# WIRELESS.net
KiCad netlist of a schematic drawn in Altium Designer
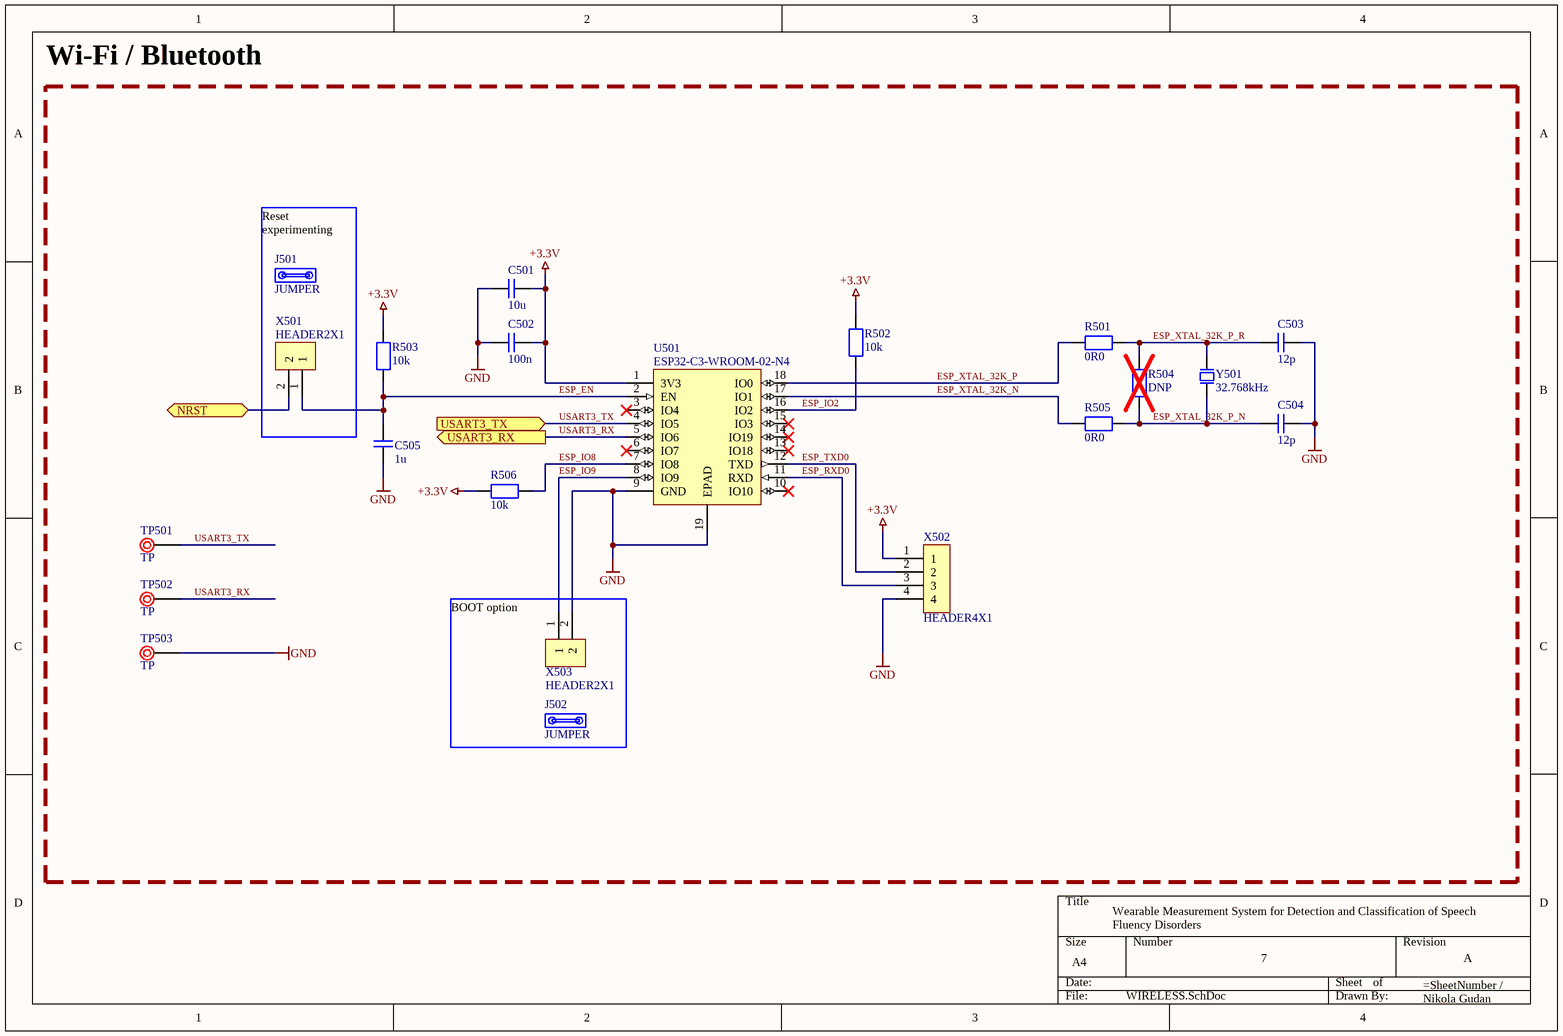
[diagram p0: WIRELESS.SchDoc]

(export (version "E")
  (design (tool "Eeschema 10.0.6"))
  (components
    (comp (ref "C501")
      (value "10u")
      (footprint "CAPC0603")
      (description "Ceramic capacitor, VAL?,  VOL?, DIEL?")
      (fields (field (name "MFR") "?") (field (name "CHECKED") "Yes"))
      (libsource (lib "NG_Passive") (part "CAPC0603"))
    )
    (comp (ref "C502")
      (value "100n")
      (footprint "CAPC0603")
      (description "Ceramic capacitor, VAL?,  VOL?, DIEL?")
      (fields (field (name "MFR") "?") (field (name "CHECKED") "Yes"))
      (libsource (lib "NG_Passive") (part "CAPC0603"))
    )
    (comp (ref "C503")
      (value "12p")
      (footprint "CAPC0603")
      (description "Ceramic capacitor, VAL?,  VOL?, DIEL?")
      (fields (field (name "MFR") "?") (field (name "CHECKED") "Yes"))
      (libsource (lib "NG_Passive") (part "CAPC0603"))
    )
    (comp (ref "C504")
      (value "12p")
      (footprint "CAPC0603")
      (description "Ceramic capacitor, VAL?,  VOL?, DIEL?")
      (fields (field (name "MFR") "?") (field (name "CHECKED") "Yes"))
      (libsource (lib "NG_Passive") (part "CAPC0603"))
    )
    (comp (ref "C505")
      (value "1u")
      (footprint "CAPC0603")
      (description "Ceramic capacitor, VAL?,  VOL?, DIEL?")
      (fields (field (name "MFR") "?") (field (name "CHECKED") "Yes"))
      (libsource (lib "NG_Passive") (part "CAPC0603"))
    )
    (comp (ref "J501")
      (value "JUMPER")
      (description "Open Top 3A 2.54mm P=2.54mm Shunts & Jumpers ROHS")
      (fields
        (field (name "MFR") "Kycon, Inc.")
        (field (name "LCSC PART NUMBER") "C5305")
        (field (name "CHECKED") "Yes")
      )
      (libsource (lib "NG_Mechanical") (part "JUMPER"))
    )
    (comp (ref "J502")
      (value "JUMPER")
      (description "Open Top 3A 2.54mm P=2.54mm Shunts & Jumpers ROHS")
      (fields
        (field (name "MFR") "Kycon, Inc.")
        (field (name "LCSC PART NUMBER") "C5305")
        (field (name "CHECKED") "Yes")
      )
      (libsource (lib "NG_Mechanical") (part "JUMPER"))
    )
    (comp (ref "R501")
      (value "0R0")
      (footprint "RESC0603")
      (description "Thick film resistor, VAL?, POW?")
      (fields (field (name "MFR") "?") (field (name "CHECKED") "Yes"))
      (libsource (lib "NG_Passive") (part "RES0603"))
    )
    (comp (ref "R502")
      (value "10k")
      (footprint "RESC0603")
      (description "Thick film resistor, VAL?, POW?")
      (fields (field (name "MFR") "?") (field (name "CHECKED") "Yes"))
      (libsource (lib "NG_Passive") (part "RES0603"))
    )
    (comp (ref "R503")
      (value "10k")
      (footprint "RESC0603")
      (description "Thick film resistor, VAL?, POW?")
      (fields (field (name "MFR") "?") (field (name "CHECKED") "Yes"))
      (libsource (lib "NG_Passive") (part "RES0603"))
    )
    (comp (ref "R504")
      (value "DNP")
      (footprint "RESC0603")
      (description "Thick film resistor, VAL?, POW?")
      (fields (field (name "MFR") "?") (field (name "CHECKED") "Yes"))
      (libsource (lib "NG_Passive") (part "RES0603"))
    )
    (comp (ref "R505")
      (value "0R0")
      (footprint "RESC0603")
      (description "Thick film resistor, VAL?, POW?")
      (fields (field (name "MFR") "?") (field (name "CHECKED") "Yes"))
      (libsource (lib "NG_Passive") (part "RES0603"))
    )
    (comp (ref "R506")
      (value "10k")
      (footprint "RESC0603")
      (description "Thick film resistor, VAL?, POW?")
      (fields (field (name "MFR") "?") (field (name "CHECKED") "Yes"))
      (libsource (lib "NG_Passive") (part "RES0603"))
    )
    (comp (ref "TP501")
      (value "TP")
      (footprint "TESTPOINT")
      (description "Testpoint")
      (fields
        (field (name "MFR") "Keystone")
        (field (name "LCSC PART NUMBER") "C238122")
        (field (name "CHECKED") "Yes")
      )
      (libsource (lib "NG_Mechanical") (part "TESTPOINT"))
    )
    (comp (ref "TP502")
      (value "TP")
      (footprint "TESTPOINT")
      (description "Testpoint")
      (fields
        (field (name "MFR") "Keystone")
        (field (name "LCSC PART NUMBER") "C238122")
        (field (name "CHECKED") "Yes")
      )
      (libsource (lib "NG_Mechanical") (part "TESTPOINT"))
    )
    (comp (ref "TP503")
      (value "TP")
      (footprint "TESTPOINT")
      (description "Testpoint")
      (fields
        (field (name "MFR") "Keystone")
        (field (name "LCSC PART NUMBER") "C238122")
        (field (name "CHECKED") "Yes")
      )
      (libsource (lib "NG_Mechanical") (part "TESTPOINT"))
    )
    (comp (ref "U501")
      (value "ESP32-C3-WROOM-02-N4")
      (footprint "ESP32-C3-WROOM-02-N4")
      (description "RF transceiver module, Bluetooth, WiFi")
      (fields
        (field (name "MFR") "Espressif Systems")
        (field (name "LCSC PART NUMBER") "C2934560")
        (field (name "CHECKED") "Yes")
      )
      (libsource (lib "NG_Digital") (part "ESP32-C3-WROOM-02-N4"))
    )
    (comp (ref "X501")
      (value "HEADER2X1")
      (footprint "HDRV2W64P254_2X1_508X254X1150")
      (description "Pin Header 2x1, P2.54")
      (fields
        (field (name "MFR") "Adam Tech")
        (field (name "LCSC PART NUMBER") "C2883961")
        (field (name "CHECKED") "Yes")
      )
      (libsource (lib "NG_Mechanical") (part "HEADER2X1"))
    )
    (comp (ref "X502")
      (value "HEADER4X1")
      (footprint "HDRV4W64P254_4X1_1016X254X1150")
      (description "Pin Header 4x1, P2.54")
      (fields (field (name "MFR") "Würth Elektronik") (field (name "CHECKED") "Yes"))
      (libsource (lib "NG_Mechanical") (part "HEADER4X1"))
    )
    (comp (ref "X503")
      (value "HEADER2X1")
      (footprint "HDRV2W64P254_2X1_508X254X1150")
      (description "Pin Header 2x1, P2.54")
      (fields
        (field (name "MFR") "Adam Tech")
        (field (name "LCSC PART NUMBER") "C2883961")
        (field (name "CHECKED") "Yes")
      )
      (libsource (lib "") (part "HEADER2X1_1"))
    )
    (comp (ref "Y501")
      (value "32.768kHz")
      (footprint "XTAL320X150X80")
      (description "Crystal, 32.768Hz, 9pF, 50kOhms")
      (fields
        (field (name "MFR") "Seiko Epson")
        (field (name "LCSC PART NUMBER") "C1987155")
        (field (name "CHECKED") "Yes")
      )
      (libsource (lib "NG_Passive") (part "X1A0001410002"))
    )
  )
  (nets
    (net (code "1") (name "+3.3V") (class "Default")
      (node (ref "C501") (pin "1") (pinfunction "1_1") (pintype "passive"))
      (node (ref "C502") (pin "1") (pinfunction "1_1") (pintype "passive"))
      (node (ref "R502") (pin "2") (pinfunction "2_2") (pintype "passive"))
      (node (ref "R503") (pin "2") (pinfunction "2_2") (pintype "passive"))
      (node (ref "R506") (pin "2") (pinfunction "2_2") (pintype "passive"))
      (node (ref "U501") (pin "1") (pinfunction "3V3_1") (pintype "power_in"))
      (node (ref "X502") (pin "1") (pinfunction "1_1") (pintype "passive"))
    )
    (net (code "2") (name "/ESP_EN") (class "Default")
      (node (ref "C505") (pin "2") (pinfunction "2_2") (pintype "passive"))
      (node (ref "R503") (pin "1") (pinfunction "1_1") (pintype "passive"))
      (node (ref "U501") (pin "2") (pinfunction "EN_2") (pintype "input"))
      (node (ref "X501") (pin "1") (pinfunction "1_1") (pintype "passive"))
    )
    (net (code "3") (name "/ESP_IO2") (class "Default")
      (node (ref "R502") (pin "1") (pinfunction "1_1") (pintype "passive"))
      (node (ref "U501") (pin "16") (pinfunction "IO2_16") (pintype "bidirectional"))
    )
    (net (code "4") (name "/ESP_IO8") (class "Default")
      (node (ref "R506") (pin "1") (pinfunction "1_1") (pintype "passive"))
      (node (ref "U501") (pin "7") (pinfunction "IO8_7") (pintype "bidirectional"))
    )
    (net (code "5") (name "/ESP_IO9") (class "Default")
      (node (ref "U501") (pin "8") (pinfunction "IO9_8") (pintype "bidirectional"))
      (node (ref "X503") (pin "1") (pinfunction "1_1") (pintype "passive"))
    )
    (net (code "6") (name "/ESP_RXD0") (class "Default")
      (node (ref "U501") (pin "11") (pinfunction "RXD_11") (pintype "input"))
      (node (ref "X502") (pin "3") (pinfunction "3_3") (pintype "passive"))
    )
    (net (code "7") (name "/ESP_TXD0") (class "Default")
      (node (ref "U501") (pin "12") (pinfunction "TXD_12") (pintype "output"))
      (node (ref "X502") (pin "2") (pinfunction "2_2") (pintype "passive"))
    )
    (net (code "8") (name "/ESP_XTAL_32K_N") (class "Default")
      (node (ref "R505") (pin "2") (pinfunction "2_2") (pintype "passive"))
      (node (ref "U501") (pin "17") (pinfunction "IO1_17") (pintype "bidirectional"))
    )
    (net (code "9") (name "/ESP_XTAL_32K_P") (class "Default")
      (node (ref "R501") (pin "2") (pinfunction "2_2") (pintype "passive"))
      (node (ref "U501") (pin "18") (pinfunction "IO0_18") (pintype "bidirectional"))
    )
    (net (code "10") (name "/ESP_XTAL_32K_P_N") (class "Default")
      (node (ref "C504") (pin "2") (pinfunction "2_2") (pintype "passive"))
      (node (ref "R504") (pin "2") (pinfunction "2_2") (pintype "passive"))
      (node (ref "R505") (pin "1") (pinfunction "1_1") (pintype "passive"))
      (node (ref "Y501") (pin "1") (pinfunction "1_1") (pintype "passive"))
    )
    (net (code "11") (name "/ESP_XTAL_32K_P_R") (class "Default")
      (node (ref "C503") (pin "2") (pinfunction "2_2") (pintype "passive"))
      (node (ref "R501") (pin "1") (pinfunction "1_1") (pintype "passive"))
      (node (ref "R504") (pin "1") (pinfunction "1_1") (pintype "passive"))
      (node (ref "Y501") (pin "2") (pinfunction "2_2") (pintype "passive"))
    )
    (net (code "12") (name "/NRST") (class "Default")
      (node (ref "X501") (pin "2") (pinfunction "2_2") (pintype "passive"))
    )
    (net (code "13") (name "/USART3_RX") (class "Default")
      (node (ref "TP502") (pin "1") (pinfunction "1_1") (pintype "passive"))
      (node (ref "U501") (pin "5") (pinfunction "IO6_5") (pintype "bidirectional"))
    )
    (net (code "14") (name "/USART3_TX") (class "Default")
      (node (ref "TP501") (pin "1") (pinfunction "1_1") (pintype "passive"))
      (node (ref "U501") (pin "4") (pinfunction "IO5_4") (pintype "bidirectional"))
    )
    (net (code "15") (name "GND") (class "Default")
      (node (ref "C501") (pin "2") (pinfunction "2_2") (pintype "passive"))
      (node (ref "C502") (pin "2") (pinfunction "2_2") (pintype "passive"))
      (node (ref "C503") (pin "1") (pinfunction "1_1") (pintype "passive"))
      (node (ref "C504") (pin "1") (pinfunction "1_1") (pintype "passive"))
      (node (ref "C505") (pin "1") (pinfunction "1_1") (pintype "passive"))
      (node (ref "TP503") (pin "1") (pinfunction "1_1") (pintype "passive"))
      (node (ref "U501") (pin "19") (pinfunction "EPAD_19") (pintype "power_in"))
      (node (ref "U501") (pin "9") (pinfunction "GND_9") (pintype "power_in"))
      (node (ref "X502") (pin "4") (pinfunction "4_4") (pintype "passive"))
      (node (ref "X503") (pin "2") (pinfunction "2_2") (pintype "passive"))
    )
    (net (code "16") (name "unconnected-(U501-IO3-Pad15)") (class "Default")
      (node (ref "U501") (pin "15") (pinfunction "IO3_15") (pintype "bidirectional+no_connect"))
    )
    (net (code "17") (name "unconnected-(U501-IO4-Pad3)") (class "Default")
      (node (ref "U501") (pin "3") (pinfunction "IO4_3") (pintype "bidirectional+no_connect"))
    )
    (net (code "18") (name "unconnected-(U501-IO7-Pad6)") (class "Default")
      (node (ref "U501") (pin "6") (pinfunction "IO7_6") (pintype "bidirectional+no_connect"))
    )
    (net (code "19") (name "unconnected-(U501-IO10-Pad10)") (class "Default")
      (node (ref "U501") (pin "10") (pinfunction "IO10_10") (pintype "bidirectional+no_connect"))
    )
    (net (code "20") (name "unconnected-(U501-IO18-Pad13)") (class "Default")
      (node (ref "U501") (pin "13") (pinfunction "IO18_13") (pintype "bidirectional+no_connect"))
    )
    (net (code "21") (name "unconnected-(U501-IO19-Pad14)") (class "Default")
      (node (ref "U501") (pin "14") (pinfunction "IO19_14") (pintype "bidirectional+no_connect"))
    )
  )
)
